# 05_Buzz_Pump_LED_Temp_ICs.net
KiCad netlist of a schematic drawn in Altium Designer
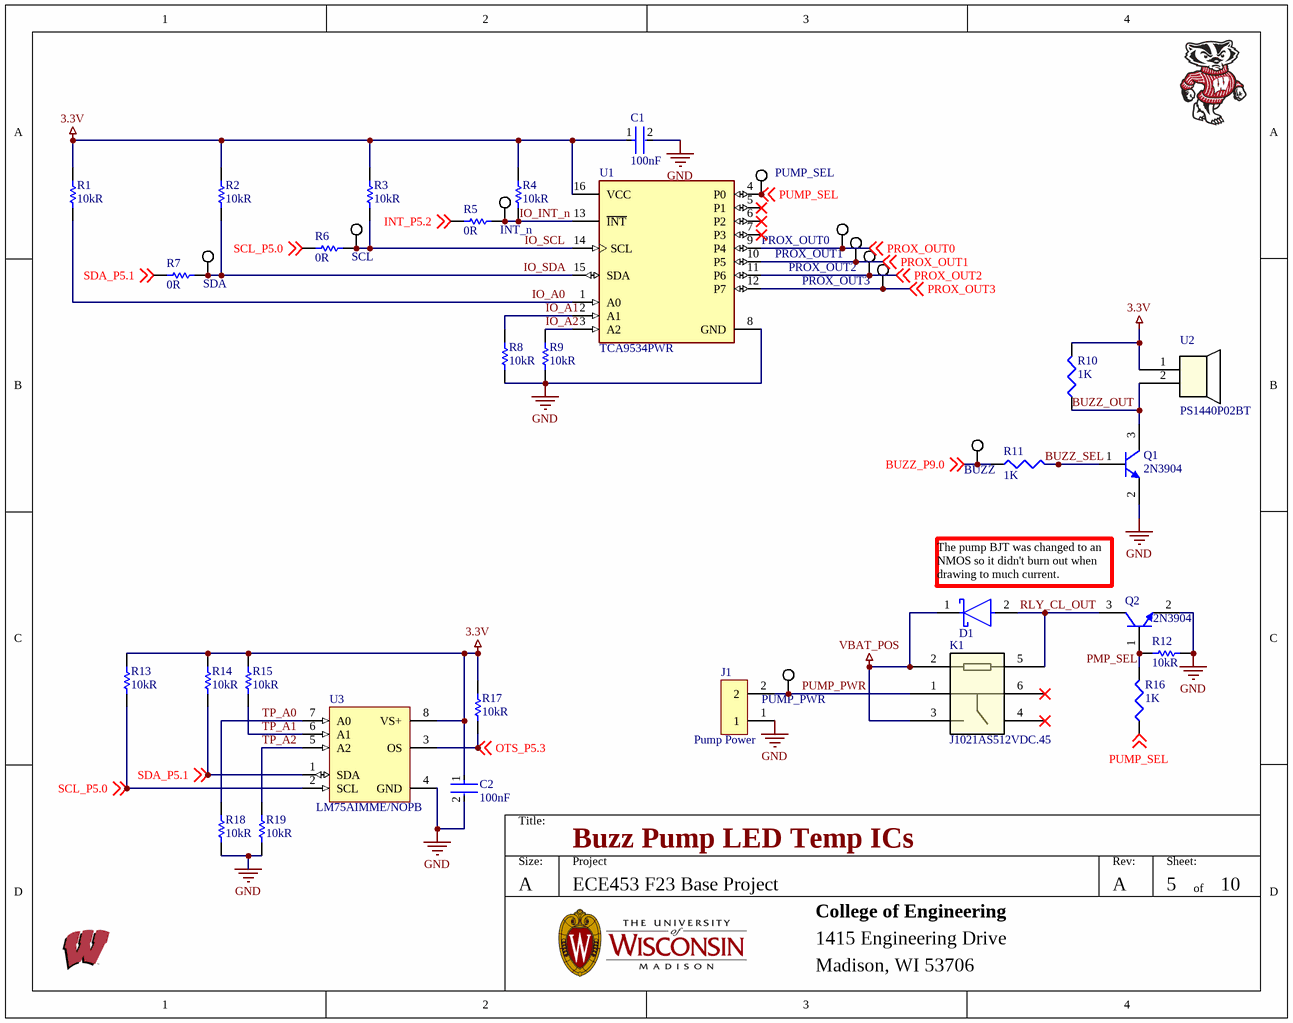
[diagram p0: 05_Buzz_Pump_LED_Temp_ICs.SchDoc]

(export (version "E")
  (design (tool "Eeschema 10.0.6"))
  (components
    (comp (ref "BUZZ")
      (value "5019")
      (footprint "KSTN-5019_V")
      (description "Test Point, 1 Position SMD, RoHS, Tape and Reel")
      (fields (field (name "MANUFACTURER") "Keystone Electronics"))
      (libsource (lib "ECE453") (part "CMP-1672-00008-1"))
    )
    (comp (ref "C1")
      (value "100nF")
      (footprint "FP-C0805C-DN-MFG")
      (description "CAP CER 0.1UF 50V X7R 0805")
      (fields
        (field (name "MANUFACTURER") "KEMET")
        (field (name "MANUFACTURER PART NUMBER") "C0805C104K5RACTU")
      )
      (libsource (lib "ECE453") (part "CMP-2007-00279-2"))
    )
    (comp (ref "C2")
      (value "100nF")
      (footprint "FP-C0805C-DN-MFG")
      (description "CAP CER 0.1UF 50V X7R 0805")
      (fields
        (field (name "MANUFACTURER") "KEMET")
        (field (name "MANUFACTURER PART NUMBER") "C0805C104K5RACTU")
      )
      (libsource (lib "ECE453") (part "CMP-2007-00279-2"))
    )
    (comp (ref "D1")
      (value "SM5817PL-TP")
      (footprint "On_Semiconductor_425-04_IPC_A")
      (description "DIODE SCHOTTKY 20V 1A SOD123FL")
      (libsource (lib "ECE453") (part "SM5817PL-TP"))
    )
    (comp (ref "INT_n")
      (value "5019")
      (footprint "KSTN-5019_V")
      (description "Test Point, 1 Position SMD, RoHS, Tape and Reel")
      (fields (field (name "MANUFACTURER") "Keystone Electronics"))
      (libsource (lib "ECE453") (part "CMP-1672-00008-1"))
    )
    (comp (ref "J1")
      (value "Pump Power")
      (footprint "PHOENIX2X0.2")
      (description "2~24 Poles, Screw Type, Horizontal, 5.08 Pitch, 26~14 (AWG), Terminal Block Connector")
      (fields
        (field (name "MANUFACTURER") "CUI Devices")
        (field (name "MANUFACTURER PART NUMBER") "TB006-508-02BE")
      )
      (libsource (lib "ECE453") (part "2-Pin"))
    )
    (comp (ref "K1")
      (value "J1021AS512VDC.45")
      (footprint "RELAY6_J102_CRS")
      (description "No Description Available")
      (fields (field (name "COPYRIGHT") "Copyright (C) 2023 Ultra Librarian. All rights reserved."))
      (libsource (lib "J1021AS512VDCP45") (part "J1021AS512VDC.45"))
    )
    (comp (ref "PROX_OUT0")
      (value "5019")
      (footprint "KSTN-5019_V")
      (description "Test Point, 1 Position SMD, RoHS, Tape and Reel")
      (fields (field (name "MANUFACTURER") "Keystone Electronics"))
      (libsource (lib "ECE453") (part "CMP-1672-00008-1"))
    )
    (comp (ref "PROX_OUT1")
      (value "5019")
      (footprint "KSTN-5019_V")
      (description "Test Point, 1 Position SMD, RoHS, Tape and Reel")
      (fields (field (name "MANUFACTURER") "Keystone Electronics"))
      (libsource (lib "ECE453") (part "CMP-1672-00008-1"))
    )
    (comp (ref "PROX_OUT2")
      (value "5019")
      (footprint "KSTN-5019_V")
      (description "Test Point, 1 Position SMD, RoHS, Tape and Reel")
      (fields (field (name "MANUFACTURER") "Keystone Electronics"))
      (libsource (lib "ECE453") (part "CMP-1672-00008-1"))
    )
    (comp (ref "PROX_OUT3")
      (value "5019")
      (footprint "KSTN-5019_V")
      (description "Test Point, 1 Position SMD, RoHS, Tape and Reel")
      (fields (field (name "MANUFACTURER") "Keystone Electronics"))
      (libsource (lib "ECE453") (part "CMP-1672-00008-1"))
    )
    (comp (ref "PUMP_PWR")
      (value "5019")
      (footprint "KSTN-5019_V")
      (description "Test Point, 1 Position SMD, RoHS, Tape and Reel")
      (fields (field (name "MANUFACTURER") "Keystone Electronics"))
      (libsource (lib "ECE453") (part "CMP-1672-00008-1"))
    )
    (comp (ref "PUMP_SEL")
      (value "5019")
      (footprint "KSTN-5019_V")
      (description "Test Point, 1 Position SMD, RoHS, Tape and Reel")
      (fields (field (name "MANUFACTURER") "Keystone Electronics"))
      (libsource (lib "ECE453") (part "CMP-1672-00008-1"))
    )
    (comp (ref "Q1")
      (value "2N3904")
      (footprint "SOT-23_M")
      (description "NPN General Purpose Amplifier")
      (fields
        (field (name "MANUFACTURER PART NUMBER") "MMBT3904-7-F")
        (field (name "MANUFACTURER") "Diodes Incorporated")
      )
      (libsource (lib "ECE453") (part "2N3904"))
    )
    (comp (ref "Q2")
      (value "2N3904")
      (footprint "SOT-23_M")
      (description "NPN General Purpose Amplifier")
      (fields
        (field (name "MANUFACTURER PART NUMBER") "MMBT3904-7-F")
        (field (name "MANUFACTURER") "Diodes Incorporated")
      )
      (libsource (lib "ECE453") (part "2N3904"))
    )
    (comp (ref "R1")
      (value "RC0805FR-0710KL")
      (footprint "RESC2013X60X35NL10T20")
      (description "Chip Resistor, 10 KOhm, +/- 1%, 0.125 W, -55 to 155 degC, 0805 (2012 Metric), RoHS, Tape and Reel")
      (fields
        (field (name "MANUFACTURER") "Yageo")
        (field (name "RESISTANCE") "10kR")
        (field (name "TOLERANCE") "1%")
      )
      (libsource (lib "ECE453") (part "CMP-1659-00013-4"))
    )
    (comp (ref "R2")
      (value "RC0805FR-0710KL")
      (footprint "RESC2013X60X35NL10T20")
      (description "Chip Resistor, 10 KOhm, +/- 1%, 0.125 W, -55 to 155 degC, 0805 (2012 Metric), RoHS, Tape and Reel")
      (fields
        (field (name "MANUFACTURER") "Yageo")
        (field (name "RESISTANCE") "10kR")
        (field (name "TOLERANCE") "1%")
      )
      (libsource (lib "ECE453") (part "CMP-1659-00013-4"))
    )
    (comp (ref "R3")
      (value "RC0805FR-0710KL")
      (footprint "RESC2013X60X35NL10T20")
      (description "Chip Resistor, 10 KOhm, +/- 1%, 0.125 W, -55 to 155 degC, 0805 (2012 Metric), RoHS, Tape and Reel")
      (fields
        (field (name "MANUFACTURER") "Yageo")
        (field (name "RESISTANCE") "10kR")
        (field (name "TOLERANCE") "1%")
      )
      (libsource (lib "ECE453") (part "CMP-1659-00013-4"))
    )
    (comp (ref "R4")
      (value "RC0805FR-0710KL")
      (footprint "RESC2013X60X35NL10T20")
      (description "Chip Resistor, 10 KOhm, +/- 1%, 0.125 W, -55 to 155 degC, 0805 (2012 Metric), RoHS, Tape and Reel")
      (fields
        (field (name "MANUFACTURER") "Yageo")
        (field (name "RESISTANCE") "10kR")
        (field (name "TOLERANCE") "1%")
      )
      (libsource (lib "ECE453") (part "CMP-1659-00013-4"))
    )
    (comp (ref "R5")
      (value "0R")
      (footprint "RESC2013X70X40NL20T20")
      (description "Chip Resistor, 0 Ohm, +/- 1%, 0.125 W, -55 to 155 degC, 0805 (2012 Metric), RoHS, Tape and Reel")
      (fields (field (name "PARTNUMBER") "ERJ-6GEY0R00V") (field (name "TOLERANCE") "5%"))
      (libsource (lib "ECE453") (part "CMP-1665-00002-5"))
    )
    (comp (ref "R6")
      (value "0R")
      (footprint "RESC2013X70X40NL20T20")
      (description "Chip Resistor, 0 Ohm, +/- 1%, 0.125 W, -55 to 155 degC, 0805 (2012 Metric), RoHS, Tape and Reel")
      (fields (field (name "PARTNUMBER") "ERJ-6GEY0R00V") (field (name "TOLERANCE") "5%"))
      (libsource (lib "ECE453") (part "CMP-1665-00002-5"))
    )
    (comp (ref "R7")
      (value "0R")
      (footprint "RESC2013X70X40NL20T20")
      (description "Chip Resistor, 0 Ohm, +/- 1%, 0.125 W, -55 to 155 degC, 0805 (2012 Metric), RoHS, Tape and Reel")
      (fields (field (name "PARTNUMBER") "ERJ-6GEY0R00V") (field (name "TOLERANCE") "5%"))
      (libsource (lib "ECE453") (part "CMP-1665-00002-5"))
    )
    (comp (ref "R8")
      (value "RC0805FR-0710KL")
      (footprint "RESC2013X60X35NL10T20")
      (description "Chip Resistor, 10 KOhm, +/- 1%, 0.125 W, -55 to 155 degC, 0805 (2012 Metric), RoHS, Tape and Reel")
      (fields
        (field (name "MANUFACTURER") "Yageo")
        (field (name "RESISTANCE") "10kR")
        (field (name "TOLERANCE") "1%")
      )
      (libsource (lib "ECE453") (part "CMP-1659-00013-4"))
    )
    (comp (ref "R9")
      (value "RC0805FR-0710KL")
      (footprint "RESC2013X60X35NL10T20")
      (description "Chip Resistor, 10 KOhm, +/- 1%, 0.125 W, -55 to 155 degC, 0805 (2012 Metric), RoHS, Tape and Reel")
      (fields
        (field (name "MANUFACTURER") "Yageo")
        (field (name "RESISTANCE") "10kR")
        (field (name "TOLERANCE") "1%")
      )
      (libsource (lib "ECE453") (part "CMP-1659-00013-4"))
    )
    (comp (ref "R10")
      (value "1K")
      (footprint "RES_0805")
      (description "Res Thick Film 0805 1K Ohm 1% 0.125W(1/8W) ±100ppm/C Pad SMD Automotive T/R")
      (fields
        (field (name "MANUFACTURER") "Stackpole Electronics")
        (field (name "MANUFACTURER PART NUMBER") "RMCF0805FT1K00")
      )
      (libsource (lib "ECE453") (part "Res3_1"))
    )
    (comp (ref "R11")
      (value "1K")
      (footprint "RES_0805")
      (description "Res Thick Film 0805 1K Ohm 1% 0.125W(1/8W) ±100ppm/C Pad SMD Automotive T/R")
      (fields
        (field (name "MANUFACTURER") "Stackpole Electronics")
        (field (name "MANUFACTURER PART NUMBER") "RMCF0805FT1K00")
      )
      (libsource (lib "ECE453") (part "Res3_1"))
    )
    (comp (ref "R12")
      (value "RC0805FR-0710KL")
      (footprint "RESC2013X60X35NL10T20")
      (description "Chip Resistor, 10 KOhm, +/- 1%, 0.125 W, -55 to 155 degC, 0805 (2012 Metric), RoHS, Tape and Reel")
      (fields
        (field (name "MANUFACTURER") "Yageo")
        (field (name "RESISTANCE") "10kR")
        (field (name "TOLERANCE") "1%")
      )
      (libsource (lib "ECE453") (part "CMP-1659-00013-4"))
    )
    (comp (ref "R13")
      (value "RC0805FR-0710KL")
      (footprint "RESC2013X60X35NL10T20")
      (description "Chip Resistor, 10 KOhm, +/- 1%, 0.125 W, -55 to 155 degC, 0805 (2012 Metric), RoHS, Tape and Reel")
      (fields
        (field (name "MANUFACTURER") "Yageo")
        (field (name "RESISTANCE") "10kR")
        (field (name "TOLERANCE") "1%")
      )
      (libsource (lib "ECE453") (part "CMP-1659-00013-4"))
    )
    (comp (ref "R14")
      (value "RC0805FR-0710KL")
      (footprint "RESC2013X60X35NL10T20")
      (description "Chip Resistor, 10 KOhm, +/- 1%, 0.125 W, -55 to 155 degC, 0805 (2012 Metric), RoHS, Tape and Reel")
      (fields
        (field (name "MANUFACTURER") "Yageo")
        (field (name "RESISTANCE") "10kR")
        (field (name "TOLERANCE") "1%")
      )
      (libsource (lib "ECE453") (part "CMP-1659-00013-4"))
    )
    (comp (ref "R15")
      (value "RC0805FR-0710KL")
      (footprint "RESC2013X60X35NL10T20")
      (description "Chip Resistor, 10 KOhm, +/- 1%, 0.125 W, -55 to 155 degC, 0805 (2012 Metric), RoHS, Tape and Reel")
      (fields
        (field (name "MANUFACTURER") "Yageo")
        (field (name "RESISTANCE") "10kR")
        (field (name "TOLERANCE") "1%")
      )
      (libsource (lib "ECE453") (part "CMP-1659-00013-4"))
    )
    (comp (ref "R16")
      (value "1K")
      (footprint "RES_0805")
      (description "Res Thick Film 0805 1K Ohm 1% 0.125W(1/8W) ±100ppm/C Pad SMD Automotive T/R")
      (fields
        (field (name "MANUFACTURER") "Stackpole Electronics")
        (field (name "MANUFACTURER PART NUMBER") "RMCF0805FT1K00")
      )
      (libsource (lib "ECE453") (part "Res3_1"))
    )
    (comp (ref "R17")
      (value "RC0805FR-0710KL")
      (footprint "RESC2013X60X35NL10T20")
      (description "Chip Resistor, 10 KOhm, +/- 1%, 0.125 W, -55 to 155 degC, 0805 (2012 Metric), RoHS, Tape and Reel")
      (fields
        (field (name "MANUFACTURER") "Yageo")
        (field (name "RESISTANCE") "10kR")
        (field (name "TOLERANCE") "1%")
      )
      (libsource (lib "ECE453") (part "CMP-1659-00013-4"))
    )
    (comp (ref "R18")
      (value "RC0805FR-0710KL")
      (footprint "RESC2013X60X35NL10T20")
      (description "Chip Resistor, 10 KOhm, +/- 1%, 0.125 W, -55 to 155 degC, 0805 (2012 Metric), RoHS, Tape and Reel")
      (fields
        (field (name "MANUFACTURER") "Yageo")
        (field (name "RESISTANCE") "10kR")
        (field (name "TOLERANCE") "1%")
      )
      (libsource (lib "ECE453") (part "CMP-1659-00013-4"))
    )
    (comp (ref "R19")
      (value "RC0805FR-0710KL")
      (footprint "RESC2013X60X35NL10T20")
      (description "Chip Resistor, 10 KOhm, +/- 1%, 0.125 W, -55 to 155 degC, 0805 (2012 Metric), RoHS, Tape and Reel")
      (fields
        (field (name "MANUFACTURER") "Yageo")
        (field (name "RESISTANCE") "10kR")
        (field (name "TOLERANCE") "1%")
      )
      (libsource (lib "ECE453") (part "CMP-1659-00013-4"))
    )
    (comp (ref "SCL")
      (value "5019")
      (footprint "KSTN-5019_V")
      (description "Test Point, 1 Position SMD, RoHS, Tape and Reel")
      (fields (field (name "MANUFACTURER") "Keystone Electronics"))
      (libsource (lib "ECE453") (part "CMP-1672-00008-1"))
    )
    (comp (ref "SDA")
      (value "5019")
      (footprint "KSTN-5019_V")
      (description "Test Point, 1 Position SMD, RoHS, Tape and Reel")
      (fields (field (name "MANUFACTURER") "Keystone Electronics"))
      (libsource (lib "ECE453") (part "CMP-1672-00008-1"))
    )
    (comp (ref "U1")
      (value "TCA9534PWR")
      (footprint "FP-PW0016A-IPC_C")
      (description "IC I/O EXPANDER I2C 8B 16TSSOP")
      (libsource (lib "ECE453") (part "CMP-04886-000003-2"))
    )
    (comp (ref "U2")
      (value "PS1440P02BT")
      (footprint "PS1440P02BT_TDK")
      (description "No Description Available")
      (fields (field (name "COPYRIGHT") "Copyright (C) 2023 Ultra Librarian. All rights reserved."))
      (libsource (lib "PS1440P02BT") (part "PS1440P02BT"))
    )
    (comp (ref "U3")
      (value "LM75AIMME/NOPB")
      (footprint "DGK0008A_L")
      (description "Digital Temperature Sensor and Thermal Watchdog with Two-Wire Interface, 8-pin Mini SOIC, Pb-Free")
      (fields (field (name "MANUFACTURER") "Texas Instruments"))
      (libsource (lib "Altium Content Vault") (part "SEN-TEMP-LM75-8"))
    )
  )
  (nets
    (net (code "1") (name "/BUZZ_OUT") (class "Default")
      (node (ref "Q1") (pin "3") (pinfunction "C_3") (pintype "passive"))
      (node (ref "R10") (pin "1") (pinfunction "1_1") (pintype "passive"))
      (node (ref "U2") (pin "2") (pinfunction "2_2") (pintype "passive"))
    )
    (net (code "2") (name "/BUZZ_SEL") (class "Default")
      (node (ref "Q1") (pin "1") (pinfunction "B_1") (pintype "passive"))
      (node (ref "R11") (pin "2") (pinfunction "2_2") (pintype "passive"))
    )
    (net (code "3") (name "/IO_A0") (class "Default")
      (node (ref "R1") (pin "1") (pinfunction "1_1") (pintype "passive"))
      (node (ref "U1") (pin "1") (pinfunction "A0_1") (pintype "input"))
    )
    (net (code "4") (name "/IO_A1") (class "Default")
      (node (ref "R8") (pin "2") (pinfunction "2_2") (pintype "passive"))
      (node (ref "U1") (pin "2") (pinfunction "A1_2") (pintype "input"))
    )
    (net (code "5") (name "/IO_A2") (class "Default")
      (node (ref "R9") (pin "2") (pinfunction "2_2") (pintype "passive"))
      (node (ref "U1") (pin "3") (pinfunction "A2_3") (pintype "input"))
    )
    (net (code "6") (name "/IO_INT_n") (class "Default")
      (node (ref "INT_n") (pin "1") (pinfunction "1_1") (pintype "passive"))
      (node (ref "R4") (pin "1") (pinfunction "1_1") (pintype "passive"))
      (node (ref "R5") (pin "2") (pinfunction "2_2") (pintype "passive"))
      (node (ref "U1") (pin "13") (pinfunction "~{INT}_13") (pintype "open_collector"))
    )
    (net (code "7") (name "/IO_SCL") (class "Default")
      (node (ref "R3") (pin "1") (pinfunction "1_1") (pintype "passive"))
      (node (ref "R6") (pin "2") (pinfunction "2_2") (pintype "passive"))
      (node (ref "SCL") (pin "1") (pinfunction "1_1") (pintype "passive"))
      (node (ref "U1") (pin "14") (pinfunction "SCL_14") (pintype "input"))
    )
    (net (code "8") (name "/IO_SDA") (class "Default")
      (node (ref "R2") (pin "1") (pinfunction "1_1") (pintype "passive"))
      (node (ref "R7") (pin "2") (pinfunction "2_2") (pintype "passive"))
      (node (ref "SDA") (pin "1") (pinfunction "1_1") (pintype "passive"))
      (node (ref "U1") (pin "15") (pinfunction "SDA_15") (pintype "bidirectional"))
    )
    (net (code "9") (name "/PMP_SEL") (class "Default")
      (node (ref "Q2") (pin "1") (pinfunction "B_1") (pintype "passive"))
      (node (ref "R12") (pin "2") (pinfunction "2_2") (pintype "passive"))
      (node (ref "R16") (pin "2") (pinfunction "2_2") (pintype "passive"))
    )
    (net (code "10") (name "/PUMP_PWR") (class "Default")
      (node (ref "J1") (pin "2") (pinfunction "2_2") (pintype "passive"))
      (node (ref "K1") (pin "1") (pinfunction "1_1") (pintype "passive"))
      (node (ref "PUMP_PWR") (pin "1") (pinfunction "1_1") (pintype "passive"))
    )
    (net (code "11") (name "/RLY_CL_OUT") (class "Default")
      (node (ref "D1") (pin "2") (pinfunction "A_2") (pintype "passive"))
      (node (ref "K1") (pin "5") (pinfunction "5_5") (pintype "passive"))
      (node (ref "Q2") (pin "3") (pinfunction "C_3") (pintype "passive"))
    )
    (net (code "12") (name "/TP_A0") (class "Default")
      (node (ref "R18") (pin "2") (pinfunction "2_2") (pintype "passive"))
      (node (ref "U3") (pin "7") (pinfunction "A0_7") (pintype "input"))
    )
    (net (code "13") (name "/TP_A1") (class "Default")
      (node (ref "R15") (pin "1") (pinfunction "1_1") (pintype "passive"))
      (node (ref "U3") (pin "6") (pinfunction "A1_6") (pintype "input"))
    )
    (net (code "14") (name "/TP_A2") (class "Default")
      (node (ref "R19") (pin "2") (pinfunction "2_2") (pintype "passive"))
      (node (ref "U3") (pin "5") (pinfunction "A2_5") (pintype "input"))
    )
    (net (code "15") (name "3.3V") (class "Default")
      (node (ref "C1") (pin "1") (pinfunction "1_1") (pintype "passive"))
      (node (ref "C2") (pin "1") (pinfunction "1_1") (pintype "passive"))
      (node (ref "R1") (pin "2") (pinfunction "2_2") (pintype "passive"))
      (node (ref "R10") (pin "2") (pinfunction "2_2") (pintype "passive"))
      (node (ref "R13") (pin "2") (pinfunction "2_2") (pintype "passive"))
      (node (ref "R14") (pin "2") (pinfunction "2_2") (pintype "passive"))
      (node (ref "R15") (pin "2") (pinfunction "2_2") (pintype "passive"))
      (node (ref "R17") (pin "2") (pinfunction "2_2") (pintype "passive"))
      (node (ref "R2") (pin "2") (pinfunction "2_2") (pintype "passive"))
      (node (ref "R3") (pin "2") (pinfunction "2_2") (pintype "passive"))
      (node (ref "R4") (pin "2") (pinfunction "2_2") (pintype "passive"))
      (node (ref "U1") (pin "16") (pinfunction "VCC_16") (pintype "power_in"))
      (node (ref "U2") (pin "1") (pinfunction "1_1") (pintype "passive"))
      (node (ref "U3") (pin "8") (pinfunction "VS+_8") (pintype "power_in"))
    )
    (net (code "16") (name "BUZZ_P9.0") (class "Default")
      (node (ref "BUZZ") (pin "1") (pinfunction "1_1") (pintype "passive"))
      (node (ref "R11") (pin "1") (pinfunction "1_1") (pintype "passive"))
    )
    (net (code "17") (name "GND") (class "Default")
      (node (ref "C1") (pin "2") (pinfunction "2_2") (pintype "passive"))
      (node (ref "C2") (pin "2") (pinfunction "2_2") (pintype "passive"))
      (node (ref "J1") (pin "1") (pinfunction "1_1") (pintype "passive"))
      (node (ref "Q1") (pin "2") (pinfunction "E_2") (pintype "passive"))
      (node (ref "Q2") (pin "2") (pinfunction "E_2") (pintype "passive"))
      (node (ref "R12") (pin "1") (pinfunction "1_1") (pintype "passive"))
      (node (ref "R18") (pin "1") (pinfunction "1_1") (pintype "passive"))
      (node (ref "R19") (pin "1") (pinfunction "1_1") (pintype "passive"))
      (node (ref "R8") (pin "1") (pinfunction "1_1") (pintype "passive"))
      (node (ref "R9") (pin "1") (pinfunction "1_1") (pintype "passive"))
      (node (ref "U1") (pin "8") (pinfunction "GND_8") (pintype "power_in"))
      (node (ref "U3") (pin "4") (pinfunction "GND_4") (pintype "power_in"))
    )
    (net (code "18") (name "INT_P5.2") (class "Default")
      (node (ref "R5") (pin "1") (pinfunction "1_1") (pintype "passive"))
    )
    (net (code "19") (name "OTS_P5.3") (class "Default")
      (node (ref "R17") (pin "1") (pinfunction "1_1") (pintype "passive"))
      (node (ref "U3") (pin "3") (pinfunction "OS_3") (pintype "open_collector"))
    )
    (net (code "20") (name "PROX_OUT0") (class "Default")
      (node (ref "PROX_OUT0") (pin "1") (pinfunction "1_1") (pintype "passive"))
      (node (ref "U1") (pin "9") (pinfunction "P4_9") (pintype "bidirectional"))
    )
    (net (code "21") (name "PROX_OUT1") (class "Default")
      (node (ref "PROX_OUT1") (pin "1") (pinfunction "1_1") (pintype "passive"))
      (node (ref "U1") (pin "10") (pinfunction "P5_10") (pintype "bidirectional"))
    )
    (net (code "22") (name "PROX_OUT2") (class "Default")
      (node (ref "PROX_OUT2") (pin "1") (pinfunction "1_1") (pintype "passive"))
      (node (ref "U1") (pin "11") (pinfunction "P6_11") (pintype "bidirectional"))
    )
    (net (code "23") (name "PROX_OUT3") (class "Default")
      (node (ref "PROX_OUT3") (pin "1") (pinfunction "1_1") (pintype "passive"))
      (node (ref "U1") (pin "12") (pinfunction "P7_12") (pintype "bidirectional"))
    )
    (net (code "24") (name "PUMP_SEL") (class "Default")
      (node (ref "PUMP_SEL") (pin "1") (pinfunction "1_1") (pintype "passive"))
      (node (ref "R16") (pin "1") (pinfunction "1_1") (pintype "passive"))
      (node (ref "U1") (pin "4") (pinfunction "P0_4") (pintype "bidirectional"))
    )
    (net (code "25") (name "SCL_P5.0") (class "Default")
      (node (ref "R13") (pin "1") (pinfunction "1_1") (pintype "passive"))
      (node (ref "R6") (pin "1") (pinfunction "1_1") (pintype "passive"))
      (node (ref "U3") (pin "2") (pinfunction "SCL_2") (pintype "input"))
    )
    (net (code "26") (name "SDA_P5.1") (class "Default")
      (node (ref "R14") (pin "1") (pinfunction "1_1") (pintype "passive"))
      (node (ref "R7") (pin "1") (pinfunction "1_1") (pintype "passive"))
      (node (ref "U3") (pin "1") (pinfunction "SDA_1") (pintype "bidirectional"))
    )
    (net (code "27") (name "VBAT_POS") (class "Default")
      (node (ref "D1") (pin "1") (pinfunction "C_1") (pintype "passive"))
      (node (ref "K1") (pin "2") (pinfunction "2_2") (pintype "passive"))
      (node (ref "K1") (pin "3") (pinfunction "3_3") (pintype "passive"))
    )
    (net (code "28") (name "unconnected-(K1-Pad4)") (class "Default")
      (node (ref "K1") (pin "4") (pinfunction "4_4") (pintype "passive+no_connect"))
    )
    (net (code "29") (name "unconnected-(K1-Pad6)") (class "Default")
      (node (ref "K1") (pin "6") (pinfunction "6_6") (pintype "passive+no_connect"))
    )
    (net (code "30") (name "unconnected-(U1-P1-Pad5)") (class "Default")
      (node (ref "U1") (pin "5") (pinfunction "P1_5") (pintype "bidirectional+no_connect"))
    )
    (net (code "31") (name "unconnected-(U1-P2-Pad6)") (class "Default")
      (node (ref "U1") (pin "6") (pinfunction "P2_6") (pintype "bidirectional+no_connect"))
    )
    (net (code "32") (name "unconnected-(U1-P3-Pad7)") (class "Default")
      (node (ref "U1") (pin "7") (pinfunction "P3_7") (pintype "bidirectional+no_connect"))
    )
  )
)
